# stm32f103cbt6.net
KiCad netlist of a schematic drawn in EAGLE
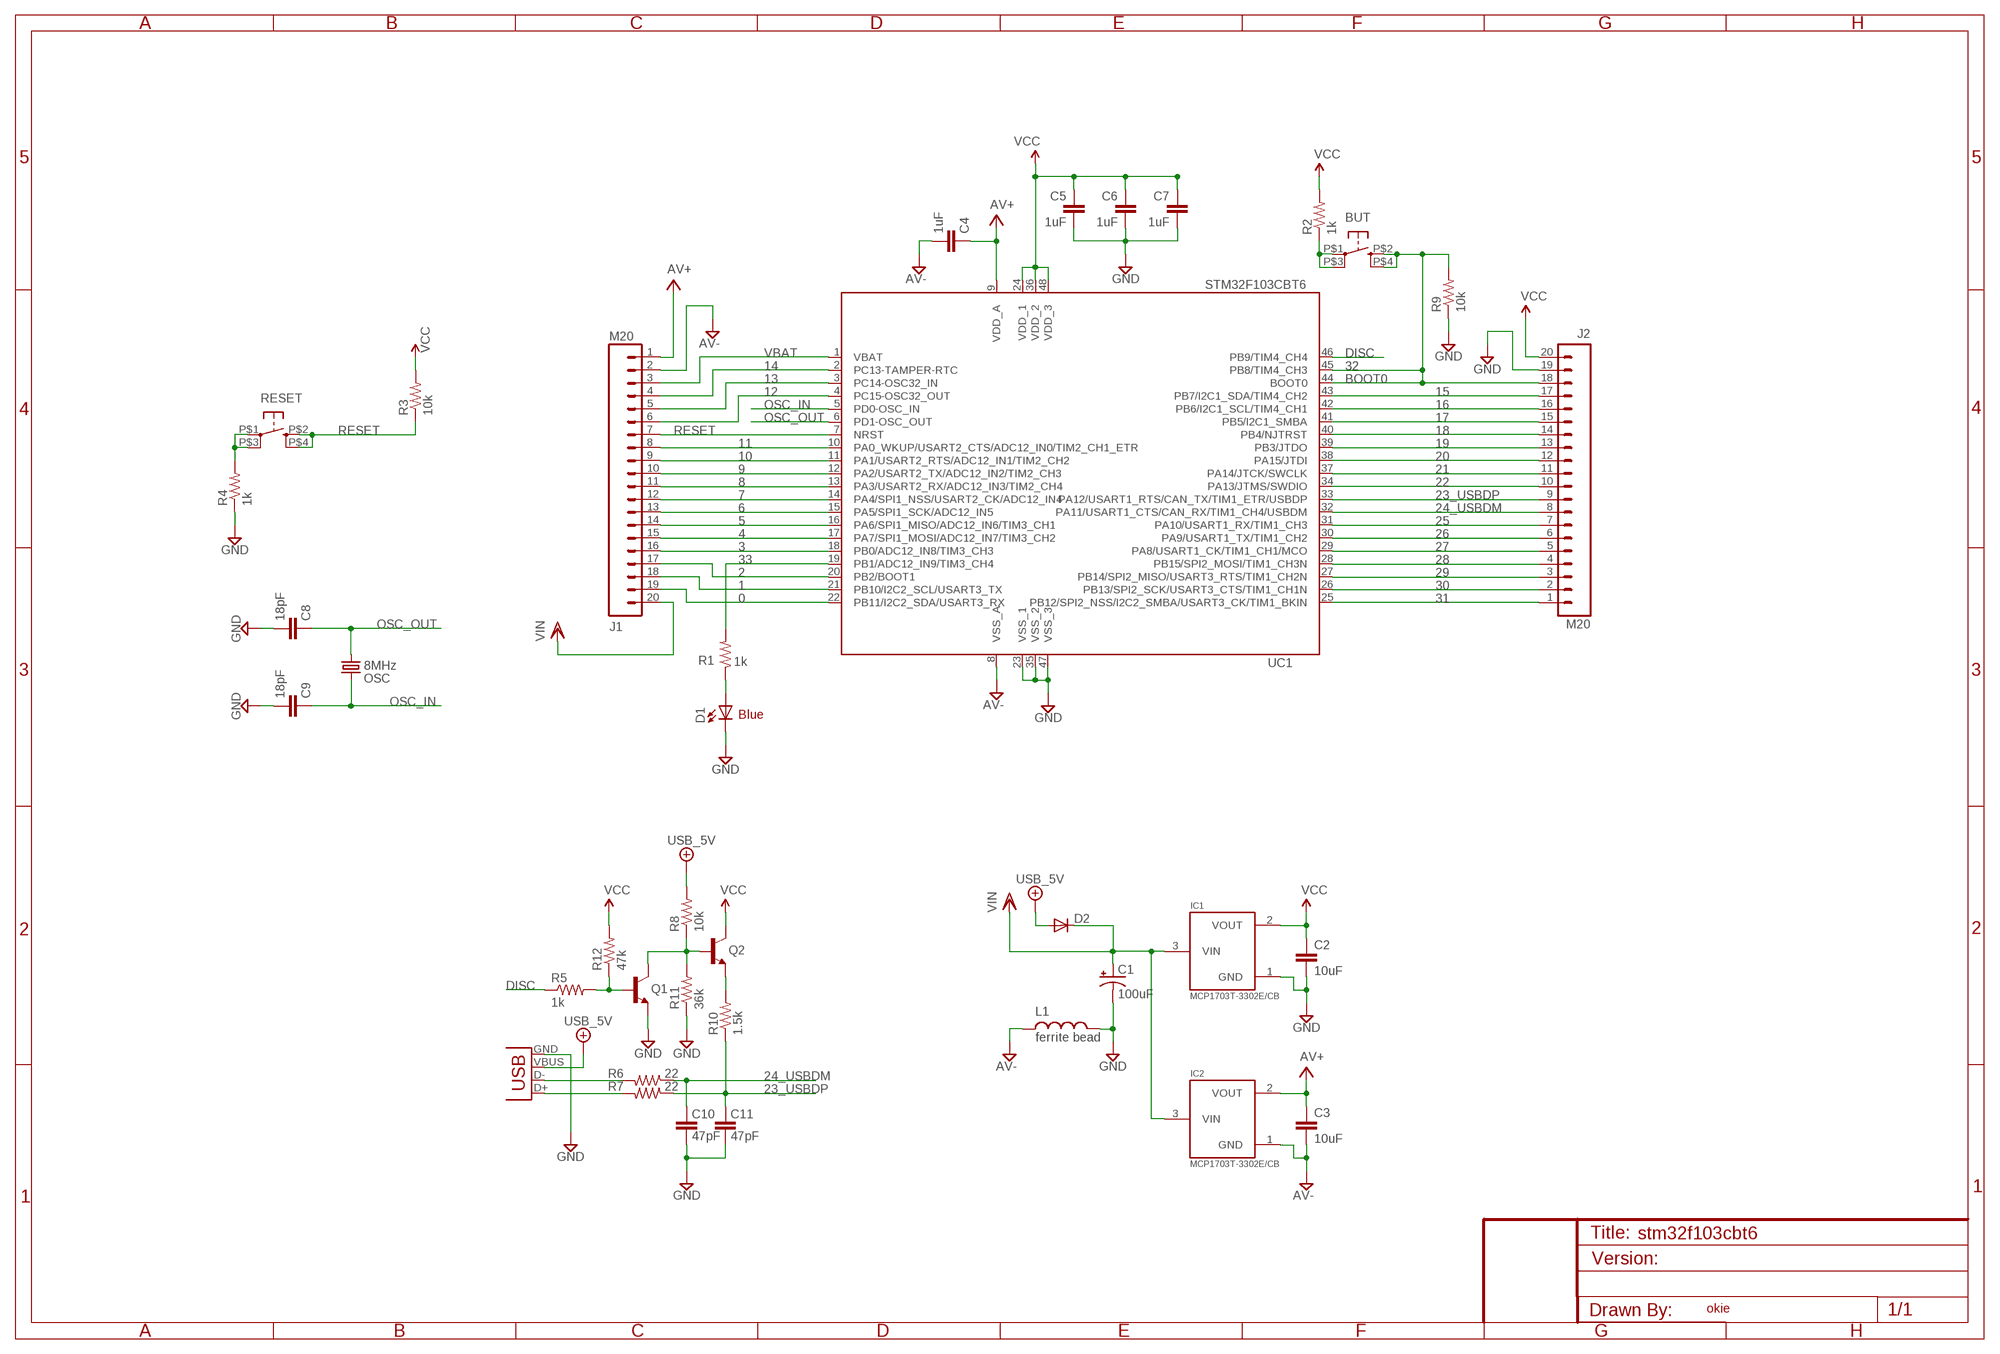
[diagram p0: schematic, sheet 1]

(export (version "E")
  (design (tool "Eeschema 10.0.6"))
  (components
    (comp (ref "BUT")
      (value "KMR211GLFS")
      (footprint "eagle-import:PUSHBUTTON-KMR241GLFS")
      (libsource (lib "eagle-import") (part "BUTTON-KMR241GLFS"))
    )
    (comp (ref "C1")
      (value "100uF")
      (footprint "eagle-import:EIA3216")
      (libsource (lib "eagle-import") (part "CAP_POL1206"))
    )
    (comp (ref "C2")
      (value "10uF")
      (footprint "eagle-import:0805")
      (libsource (lib "eagle-import") (part "SparkFun2_CAP0805"))
    )
    (comp (ref "C3")
      (value "10uF")
      (footprint "eagle-import:0805")
      (libsource (lib "eagle-import") (part "SparkFun2_CAP0805"))
    )
    (comp (ref "C4")
      (value "1uF")
      (footprint "eagle-import:C0402")
      (libsource (lib "eagle-import") (part "CAP0402"))
    )
    (comp (ref "C5")
      (value "1uF")
      (footprint "eagle-import:C0402")
      (libsource (lib "eagle-import") (part "CAP0402"))
    )
    (comp (ref "C6")
      (value "1uF")
      (footprint "eagle-import:C0402")
      (libsource (lib "eagle-import") (part "CAP0402"))
    )
    (comp (ref "C7")
      (value "1uF")
      (footprint "eagle-import:C0402")
      (libsource (lib "eagle-import") (part "CAP0402"))
    )
    (comp (ref "C8")
      (value "18pF")
      (footprint "eagle-import:C0402")
      (libsource (lib "eagle-import") (part "CAP0402"))
    )
    (comp (ref "C9")
      (value "18pF")
      (footprint "eagle-import:C0402")
      (libsource (lib "eagle-import") (part "CAP0402"))
    )
    (comp (ref "C10")
      (value "47pF")
      (footprint "eagle-import:C0402")
      (libsource (lib "eagle-import") (part "CAP0402"))
    )
    (comp (ref "C11")
      (value "47pF")
      (footprint "eagle-import:C0402")
      (libsource (lib "eagle-import") (part "CAP0402"))
    )
    (comp (ref "D1")
      (value "Blue")
      (footprint "eagle-import:LED-1206")
      (libsource (lib "eagle-import") (part "LED1206"))
    )
    (comp (ref "D2")
      (value "DIODESOD")
      (footprint "eagle-import:SOD-323")
      (libsource (lib "eagle-import") (part "DIODESOD"))
    )
    (comp (ref "IC1")
      (value "MCP1703T-3302E/CB")
      (footprint "eagle-import:SOT23")
      (libsource (lib "eagle-import") (part "MCP1700T"))
    )
    (comp (ref "IC2")
      (value "MCP1703T-3302E/CB")
      (footprint "eagle-import:SOT23")
      (libsource (lib "eagle-import") (part "MCP1700T"))
    )
    (comp (ref "J1")
      (value "M20")
      (footprint "eagle-import:1X20")
      (libsource (lib "eagle-import") (part "M20"))
    )
    (comp (ref "J2")
      (value "M20")
      (footprint "eagle-import:1X20")
      (libsource (lib "eagle-import") (part "M20"))
    )
    (comp (ref "L1")
      (value "ferrite bead")
      (footprint "eagle-import:0603")
      (libsource (lib "eagle-import") (part "INDUCTOR0603"))
    )
    (comp (ref "OSC")
      (value "8MHz")
      (footprint "eagle-import:CRYSTAL-SMD-5X3")
      (libsource (lib "eagle-import") (part "CRYSTAL5X3"))
    )
    (comp (ref "Q1")
      (value "NPN-BJT")
      (footprint "eagle-import:SOT23")
      (libsource (lib "eagle-import") (part "TRANSISTOR_NPNSOT23"))
    )
    (comp (ref "Q2")
      (value "NPN-BJT")
      (footprint "eagle-import:SOT23")
      (libsource (lib "eagle-import") (part "TRANSISTOR_NPNSOT23"))
    )
    (comp (ref "R1")
      (value "1k")
      (footprint "eagle-import:C0402")
      (libsource (lib "eagle-import") (part "RESISTOR0402"))
    )
    (comp (ref "R2")
      (value "1k")
      (footprint "eagle-import:C0402")
      (libsource (lib "eagle-import") (part "RESISTOR0402"))
    )
    (comp (ref "R3")
      (value "10k")
      (footprint "eagle-import:C0402")
      (libsource (lib "eagle-import") (part "RESISTOR0402"))
    )
    (comp (ref "R4")
      (value "1k")
      (footprint "eagle-import:C0402")
      (libsource (lib "eagle-import") (part "RESISTOR0402"))
    )
    (comp (ref "R5")
      (value "1k")
      (footprint "eagle-import:C0402")
      (libsource (lib "eagle-import") (part "RESISTOR0402"))
    )
    (comp (ref "R6")
      (value "22")
      (footprint "eagle-import:C0402")
      (libsource (lib "eagle-import") (part "RESISTOR0402"))
    )
    (comp (ref "R7")
      (value "22")
      (footprint "eagle-import:C0402")
      (libsource (lib "eagle-import") (part "RESISTOR0402"))
    )
    (comp (ref "R8")
      (value "10k")
      (footprint "eagle-import:C0402")
      (libsource (lib "eagle-import") (part "RESISTOR0402"))
    )
    (comp (ref "R9")
      (value "10k")
      (footprint "eagle-import:C0402")
      (libsource (lib "eagle-import") (part "RESISTOR0402"))
    )
    (comp (ref "R10")
      (value "1.5k")
      (footprint "eagle-import:C0402")
      (libsource (lib "eagle-import") (part "RESISTOR0402"))
    )
    (comp (ref "R11")
      (value "36k")
      (footprint "eagle-import:C0402")
      (libsource (lib "eagle-import") (part "RESISTOR0402"))
    )
    (comp (ref "R12")
      (value "47k")
      (footprint "eagle-import:C0402")
      (libsource (lib "eagle-import") (part "RESISTOR0402"))
    )
    (comp (ref "RESET")
      (value "KMR211GLFS")
      (footprint "eagle-import:PUSHBUTTON-KMR241GLFS")
      (libsource (lib "eagle-import") (part "BUTTON-KMR241GLFS"))
    )
    (comp (ref "UC1")
      (value "STM32F103CBT6")
      (footprint "eagle-import:LQFP48")
      (libsource (lib "eagle-import") (part "STM32F103CB"))
    )
    (comp (ref "X1")
      (value "USB-MINIB")
      (footprint "eagle-import:USB-MINIB")
      (libsource (lib "eagle-import") (part "USBSMD"))
    )
  )
  (nets
    (net (code "1") (name "/0") (class "Default")
      (node (ref "J1") (pin "19") (pinfunction "19_19") (pintype "passive"))
      (node (ref "UC1") (pin "22") (pinfunction "PB11/I2C2_SDA/USART3_RX_22") (pintype "input"))
    )
    (net (code "2") (name "/1") (class "Default")
      (node (ref "J1") (pin "18") (pinfunction "18_18") (pintype "passive"))
      (node (ref "UC1") (pin "21") (pinfunction "PB10/I2C2_SCL/USART3_TX_21") (pintype "input"))
    )
    (net (code "3") (name "/2") (class "Default")
      (node (ref "J1") (pin "17") (pinfunction "17_17") (pintype "passive"))
      (node (ref "UC1") (pin "20") (pinfunction "PB2/BOOT1_20") (pintype "bidirectional"))
    )
    (net (code "4") (name "/3") (class "Default")
      (node (ref "J1") (pin "16") (pinfunction "16_16") (pintype "passive"))
      (node (ref "UC1") (pin "18") (pinfunction "PB0/ADC12_IN8/TIM3_CH3_18") (pintype "bidirectional"))
    )
    (net (code "5") (name "/4") (class "Default")
      (node (ref "J1") (pin "15") (pinfunction "15_15") (pintype "passive"))
      (node (ref "UC1") (pin "17") (pinfunction "PA7/SPI1_MOSI/ADC12_IN7/TIM3_CH2_17") (pintype "bidirectional"))
    )
    (net (code "6") (name "/5") (class "Default")
      (node (ref "J1") (pin "14") (pinfunction "14_14") (pintype "passive"))
      (node (ref "UC1") (pin "16") (pinfunction "PA6/SPI1_MISO/ADC12_IN6/TIM3_CH1_16") (pintype "bidirectional"))
    )
    (net (code "7") (name "/6") (class "Default")
      (node (ref "J1") (pin "13") (pinfunction "13_13") (pintype "passive"))
      (node (ref "UC1") (pin "15") (pinfunction "PA5/SPI1_SCK/ADC12_IN5_15") (pintype "bidirectional"))
    )
    (net (code "8") (name "/7") (class "Default")
      (node (ref "J1") (pin "12") (pinfunction "12_12") (pintype "passive"))
      (node (ref "UC1") (pin "14") (pinfunction "PA4/SPI1_NSS/USART2_CK/ADC12_IN4_14") (pintype "bidirectional"))
    )
    (net (code "9") (name "/8") (class "Default")
      (node (ref "J1") (pin "11") (pinfunction "11_11") (pintype "passive"))
      (node (ref "UC1") (pin "13") (pinfunction "PA3/USART2_RX/ADC12_IN3/TIM2_CH4_13") (pintype "bidirectional"))
    )
    (net (code "10") (name "/9") (class "Default")
      (node (ref "J1") (pin "10") (pinfunction "10_10") (pintype "passive"))
      (node (ref "UC1") (pin "12") (pinfunction "PA2/USART2_TX/ADC12_IN2/TIM2_CH3_12") (pintype "bidirectional"))
    )
    (net (code "11") (name "/10") (class "Default")
      (node (ref "J1") (pin "9") (pinfunction "9_9") (pintype "passive"))
      (node (ref "UC1") (pin "11") (pinfunction "PA1/USART2_RTS/ADC12_IN1/TIM2_CH2_11") (pintype "bidirectional"))
    )
    (net (code "12") (name "/11") (class "Default")
      (node (ref "J1") (pin "8") (pinfunction "8_8") (pintype "passive"))
      (node (ref "UC1") (pin "10") (pinfunction "PA0_WKUP/USART2_CTS/ADC12_IN0/TIM2_CH1_ETR_10") (pintype "bidirectional"))
    )
    (net (code "13") (name "/12") (class "Default")
      (node (ref "J1") (pin "6") (pinfunction "6_6") (pintype "passive"))
      (node (ref "UC1") (pin "4") (pinfunction "PC15-OSC32_OUT_4") (pintype "input"))
    )
    (net (code "14") (name "/13") (class "Default")
      (node (ref "J1") (pin "5") (pinfunction "5_5") (pintype "passive"))
      (node (ref "UC1") (pin "3") (pinfunction "PC14-OSC32_IN_3") (pintype "input"))
    )
    (net (code "15") (name "/14") (class "Default")
      (node (ref "J1") (pin "4") (pinfunction "4_4") (pintype "passive"))
      (node (ref "UC1") (pin "2") (pinfunction "PC13-TAMPER-RTC_2") (pintype "input"))
    )
    (net (code "16") (name "/15") (class "Default")
      (node (ref "J2") (pin "17") (pinfunction "17_17") (pintype "passive"))
      (node (ref "UC1") (pin "43") (pinfunction "PB7/I2C1_SDA/TIM4_CH2_43") (pintype "bidirectional"))
    )
    (net (code "17") (name "/16") (class "Default")
      (node (ref "J2") (pin "16") (pinfunction "16_16") (pintype "passive"))
      (node (ref "UC1") (pin "42") (pinfunction "PB6/I2C1_SCL/TIM4_CH1_42") (pintype "input"))
    )
    (net (code "18") (name "/17") (class "Default")
      (node (ref "J2") (pin "15") (pinfunction "15_15") (pintype "passive"))
      (node (ref "UC1") (pin "41") (pinfunction "PB5/I2C1_SMBA_41") (pintype "input"))
    )
    (net (code "19") (name "/18") (class "Default")
      (node (ref "J2") (pin "14") (pinfunction "14_14") (pintype "passive"))
      (node (ref "UC1") (pin "40") (pinfunction "PB4/NJTRST_40") (pintype "bidirectional"))
    )
    (net (code "20") (name "/19") (class "Default")
      (node (ref "J2") (pin "13") (pinfunction "13_13") (pintype "passive"))
      (node (ref "UC1") (pin "39") (pinfunction "PB3/JTDO_39") (pintype "bidirectional"))
    )
    (net (code "21") (name "/20") (class "Default")
      (node (ref "J2") (pin "12") (pinfunction "12_12") (pintype "passive"))
      (node (ref "UC1") (pin "38") (pinfunction "PA15/JTDI_38") (pintype "bidirectional"))
    )
    (net (code "22") (name "/21") (class "Default")
      (node (ref "J2") (pin "11") (pinfunction "11_11") (pintype "passive"))
      (node (ref "UC1") (pin "37") (pinfunction "PA14/JTCK/SWCLK_37") (pintype "bidirectional"))
    )
    (net (code "23") (name "/22") (class "Default")
      (node (ref "J2") (pin "10") (pinfunction "10_10") (pintype "passive"))
      (node (ref "UC1") (pin "34") (pinfunction "PA13/JTMS/SWDIO_34") (pintype "bidirectional"))
    )
    (net (code "24") (name "/23_USBDP") (class "Default")
      (node (ref "C11") (pin "2") (pinfunction "2_2") (pintype "passive"))
      (node (ref "J2") (pin "9") (pinfunction "9_9") (pintype "passive"))
      (node (ref "R10") (pin "1") (pinfunction "1_1") (pintype "passive"))
      (node (ref "R7") (pin "1") (pinfunction "1_1") (pintype "passive"))
      (node (ref "UC1") (pin "33") (pinfunction "PA12/USART1_RTS/CAN_TX/TIM1_ETR/USBDP_33") (pintype "bidirectional"))
    )
    (net (code "25") (name "/24_USBDM") (class "Default")
      (node (ref "C10") (pin "2") (pinfunction "2_2") (pintype "passive"))
      (node (ref "J2") (pin "8") (pinfunction "8_8") (pintype "passive"))
      (node (ref "R6") (pin "1") (pinfunction "1_1") (pintype "passive"))
      (node (ref "UC1") (pin "32") (pinfunction "PA11/USART1_CTS/CAN_RX/TIM1_CH4/USBDM_32") (pintype "bidirectional"))
    )
    (net (code "26") (name "/25") (class "Default")
      (node (ref "J2") (pin "7") (pinfunction "7_7") (pintype "passive"))
      (node (ref "UC1") (pin "31") (pinfunction "PA10/USART1_RX/TIM1_CH3_31") (pintype "bidirectional"))
    )
    (net (code "27") (name "/26") (class "Default")
      (node (ref "J2") (pin "6") (pinfunction "6_6") (pintype "passive"))
      (node (ref "UC1") (pin "30") (pinfunction "PA9/USART1_TX/TIM1_CH2_30") (pintype "input"))
    )
    (net (code "28") (name "/27") (class "Default")
      (node (ref "J2") (pin "5") (pinfunction "5_5") (pintype "passive"))
      (node (ref "UC1") (pin "29") (pinfunction "PA8/USART1_CK/TIM1_CH1/MCO_29") (pintype "bidirectional"))
    )
    (net (code "29") (name "/28") (class "Default")
      (node (ref "J2") (pin "4") (pinfunction "4_4") (pintype "passive"))
      (node (ref "UC1") (pin "28") (pinfunction "PB15/SPI2_MOSI/TIM1_CH3N_28") (pintype "input"))
    )
    (net (code "30") (name "/29") (class "Default")
      (node (ref "J2") (pin "3") (pinfunction "3_3") (pintype "passive"))
      (node (ref "UC1") (pin "27") (pinfunction "PB14/SPI2_MISO/USART3_RTS/TIM1_CH2N_27") (pintype "input"))
    )
    (net (code "31") (name "/30") (class "Default")
      (node (ref "J2") (pin "2") (pinfunction "2_2") (pintype "passive"))
      (node (ref "UC1") (pin "26") (pinfunction "PB13/SPI2_SCK/USART3_CTS/TIM1_CH1N_26") (pintype "input"))
    )
    (net (code "32") (name "/31") (class "Default")
      (node (ref "J2") (pin "1") (pinfunction "1_1") (pintype "passive"))
      (node (ref "UC1") (pin "25") (pinfunction "PB12/SPI2_NSS/I2C2_SMBA/USART3_CK/TIM1_BKIN_25") (pintype "input"))
    )
    (net (code "33") (name "/32") (class "Default")
      (node (ref "BUT") (pin "P$2") (pinfunction "2_P$2") (pintype "passive"))
      (node (ref "BUT") (pin "P$4") (pinfunction "4_P$4") (pintype "passive"))
      (node (ref "J2") (pin "18") (pinfunction "18_18") (pintype "passive"))
      (node (ref "R9") (pin "2") (pinfunction "2_2") (pintype "passive"))
      (node (ref "UC1") (pin "44") (pinfunction "BOOT0_44") (pintype "input"))
      (node (ref "UC1") (pin "45") (pinfunction "PB8/TIM4_CH3_45") (pintype "bidirectional"))
    )
    (net (code "34") (name "/33") (class "Default")
      (node (ref "R1") (pin "2") (pinfunction "2_2") (pintype "passive"))
      (node (ref "UC1") (pin "19") (pinfunction "PB1/ADC12_IN9/TIM3_CH4_19") (pintype "bidirectional"))
    )
    (net (code "35") (name "/DISC") (class "Default")
      (node (ref "R5") (pin "1") (pinfunction "1_1") (pintype "passive"))
      (node (ref "UC1") (pin "46") (pinfunction "PB9/TIM4_CH4_46") (pintype "input"))
    )
    (net (code "36") (name "/OSC_IN") (class "Default")
      (node (ref "C9") (pin "1") (pinfunction "1_1") (pintype "passive"))
      (node (ref "OSC") (pin "3") (pinfunction "2_3") (pintype "passive"))
      (node (ref "UC1") (pin "5") (pinfunction "PD0-OSC_IN_5") (pintype "input"))
    )
    (net (code "37") (name "/OSC_OUT") (class "Default")
      (node (ref "C8") (pin "1") (pinfunction "1_1") (pintype "passive"))
      (node (ref "OSC") (pin "1") (pinfunction "1_1") (pintype "passive"))
      (node (ref "UC1") (pin "6") (pinfunction "PD1-OSC_OUT_6") (pintype "input"))
    )
    (net (code "38") (name "/RESET") (class "Default")
      (node (ref "J1") (pin "7") (pinfunction "7_7") (pintype "passive"))
      (node (ref "R3") (pin "1") (pinfunction "1_1") (pintype "passive"))
      (node (ref "RESET") (pin "P$2") (pinfunction "2_P$2") (pintype "passive"))
      (node (ref "RESET") (pin "P$4") (pinfunction "4_P$4") (pintype "passive"))
      (node (ref "UC1") (pin "7") (pinfunction "NRST_7") (pintype "input"))
    )
    (net (code "39") (name "/VBAT") (class "Default")
      (node (ref "J1") (pin "3") (pinfunction "3_3") (pintype "passive"))
      (node (ref "UC1") (pin "1") (pinfunction "VBAT_1") (pintype "power_in"))
    )
    (net (code "40") (name "AV+") (class "Default")
      (node (ref "C3") (pin "1") (pinfunction "1_1") (pintype "passive"))
      (node (ref "C4") (pin "1") (pinfunction "1_1") (pintype "passive"))
      (node (ref "IC2") (pin "2") (pinfunction "VOUT_2") (pintype "bidirectional"))
      (node (ref "J1") (pin "1") (pinfunction "1_1") (pintype "passive"))
      (node (ref "UC1") (pin "9") (pinfunction "VDD_A_9") (pintype "power_in"))
    )
    (net (code "41") (name "AV-") (class "Default")
      (node (ref "C3") (pin "2") (pinfunction "2_2") (pintype "passive"))
      (node (ref "C4") (pin "2") (pinfunction "2_2") (pintype "passive"))
      (node (ref "IC2") (pin "1") (pinfunction "GND_1") (pintype "bidirectional"))
      (node (ref "J1") (pin "2") (pinfunction "2_2") (pintype "passive"))
      (node (ref "L1") (pin "1") (pinfunction "1_1") (pintype "passive"))
      (node (ref "UC1") (pin "8") (pinfunction "VSS_A_8") (pintype "power_in"))
    )
    (net (code "42") (name "GND") (class "Default")
      (node (ref "C1") (pin "C") (pinfunction "-_C") (pintype "passive"))
      (node (ref "C10") (pin "1") (pinfunction "1_1") (pintype "passive"))
      (node (ref "C11") (pin "1") (pinfunction "1_1") (pintype "passive"))
      (node (ref "C2") (pin "2") (pinfunction "2_2") (pintype "passive"))
      (node (ref "C5") (pin "2") (pinfunction "2_2") (pintype "passive"))
      (node (ref "C6") (pin "2") (pinfunction "2_2") (pintype "passive"))
      (node (ref "C7") (pin "2") (pinfunction "2_2") (pintype "passive"))
      (node (ref "C8") (pin "2") (pinfunction "2_2") (pintype "passive"))
      (node (ref "C9") (pin "2") (pinfunction "2_2") (pintype "passive"))
      (node (ref "D1") (pin "C") (pinfunction "C_C") (pintype "passive"))
      (node (ref "IC1") (pin "1") (pinfunction "GND_1") (pintype "bidirectional"))
      (node (ref "J2") (pin "19") (pinfunction "19_19") (pintype "passive"))
      (node (ref "L1") (pin "2") (pinfunction "2_2") (pintype "passive"))
      (node (ref "Q1") (pin "2") (pinfunction "E_2") (pintype "passive"))
      (node (ref "R11") (pin "1") (pinfunction "1_1") (pintype "passive"))
      (node (ref "R4") (pin "1") (pinfunction "1_1") (pintype "passive"))
      (node (ref "R9") (pin "1") (pinfunction "1_1") (pintype "passive"))
      (node (ref "UC1") (pin "23") (pinfunction "VSS_1_23") (pintype "power_in"))
      (node (ref "UC1") (pin "35") (pinfunction "VSS_2_35") (pintype "power_in"))
      (node (ref "UC1") (pin "47") (pinfunction "VSS_3_47") (pintype "power_in"))
      (node (ref "X1") (pin "GND") (pinfunction "GND_GND") (pintype "bidirectional"))
    )
    (net (code "43") (name "Net-(BUT-1)") (class "Default")
      (node (ref "BUT") (pin "P$1") (pinfunction "1_P$1") (pintype "passive"))
      (node (ref "BUT") (pin "P$3") (pinfunction "3_P$3") (pintype "passive"))
      (node (ref "R2") (pin "1") (pinfunction "1_1") (pintype "passive"))
    )
    (net (code "44") (name "Net-(D1-PadA)") (class "Default")
      (node (ref "D1") (pin "A") (pinfunction "A_A") (pintype "passive"))
      (node (ref "R1") (pin "1") (pinfunction "1_1") (pintype "passive"))
    )
    (net (code "45") (name "Net-(Q1-B)") (class "Default")
      (node (ref "Q1") (pin "1") (pinfunction "B_1") (pintype "passive"))
      (node (ref "R12") (pin "1") (pinfunction "1_1") (pintype "passive"))
      (node (ref "R5") (pin "2") (pinfunction "2_2") (pintype "passive"))
    )
    (net (code "46") (name "Net-(Q1-C)") (class "Default")
      (node (ref "Q1") (pin "3") (pinfunction "C_3") (pintype "passive"))
      (node (ref "Q2") (pin "1") (pinfunction "B_1") (pintype "passive"))
      (node (ref "R11") (pin "2") (pinfunction "2_2") (pintype "passive"))
      (node (ref "R8") (pin "1") (pinfunction "1_1") (pintype "passive"))
    )
    (net (code "47") (name "Net-(Q2-E)") (class "Default")
      (node (ref "Q2") (pin "2") (pinfunction "E_2") (pintype "passive"))
      (node (ref "R10") (pin "2") (pinfunction "2_2") (pintype "passive"))
    )
    (net (code "48") (name "Net-(R6-Pad2)") (class "Default")
      (node (ref "R6") (pin "2") (pinfunction "2_2") (pintype "passive"))
      (node (ref "X1") (pin "D-") (pinfunction "D-_D-") (pintype "bidirectional"))
    )
    (net (code "49") (name "Net-(R7-Pad2)") (class "Default")
      (node (ref "R7") (pin "2") (pinfunction "2_2") (pintype "passive"))
      (node (ref "X1") (pin "D+") (pinfunction "D+_D+") (pintype "bidirectional"))
    )
    (net (code "50") (name "Net-(RESET-1)") (class "Default")
      (node (ref "R4") (pin "2") (pinfunction "2_2") (pintype "passive"))
      (node (ref "RESET") (pin "P$1") (pinfunction "1_P$1") (pintype "passive"))
      (node (ref "RESET") (pin "P$3") (pinfunction "3_P$3") (pintype "passive"))
    )
    (net (code "51") (name "USB_5V") (class "Default")
      (node (ref "D2") (pin "2") (pinfunction "A_2") (pintype "passive"))
      (node (ref "R8") (pin "2") (pinfunction "2_2") (pintype "passive"))
      (node (ref "X1") (pin "VBUS") (pinfunction "VBUS_VBUS") (pintype "bidirectional"))
    )
    (net (code "52") (name "VCC") (class "Default")
      (node (ref "C2") (pin "1") (pinfunction "1_1") (pintype "passive"))
      (node (ref "C5") (pin "1") (pinfunction "1_1") (pintype "passive"))
      (node (ref "C6") (pin "1") (pinfunction "1_1") (pintype "passive"))
      (node (ref "C7") (pin "1") (pinfunction "1_1") (pintype "passive"))
      (node (ref "IC1") (pin "2") (pinfunction "VOUT_2") (pintype "bidirectional"))
      (node (ref "J2") (pin "20") (pinfunction "20_20") (pintype "passive"))
      (node (ref "Q2") (pin "3") (pinfunction "C_3") (pintype "passive"))
      (node (ref "R12") (pin "2") (pinfunction "2_2") (pintype "passive"))
      (node (ref "R2") (pin "2") (pinfunction "2_2") (pintype "passive"))
      (node (ref "R3") (pin "2") (pinfunction "2_2") (pintype "passive"))
      (node (ref "UC1") (pin "24") (pinfunction "VDD_1_24") (pintype "power_in"))
      (node (ref "UC1") (pin "36") (pinfunction "VDD_2_36") (pintype "power_in"))
      (node (ref "UC1") (pin "48") (pinfunction "VDD_3_48") (pintype "power_in"))
    )
    (net (code "53") (name "VIN") (class "Default")
      (node (ref "C1") (pin "A") (pinfunction "+_A") (pintype "passive"))
      (node (ref "D2") (pin "1") (pinfunction "C_1") (pintype "passive"))
      (node (ref "IC1") (pin "3") (pinfunction "VIN_3") (pintype "bidirectional"))
      (node (ref "IC2") (pin "3") (pinfunction "VIN_3") (pintype "bidirectional"))
      (node (ref "J1") (pin "20") (pinfunction "20_20") (pintype "passive"))
    )
  )
)
